# Led_sensor_board_wiring.net
KiCad netlist of a schematic drawn in Altium Designer
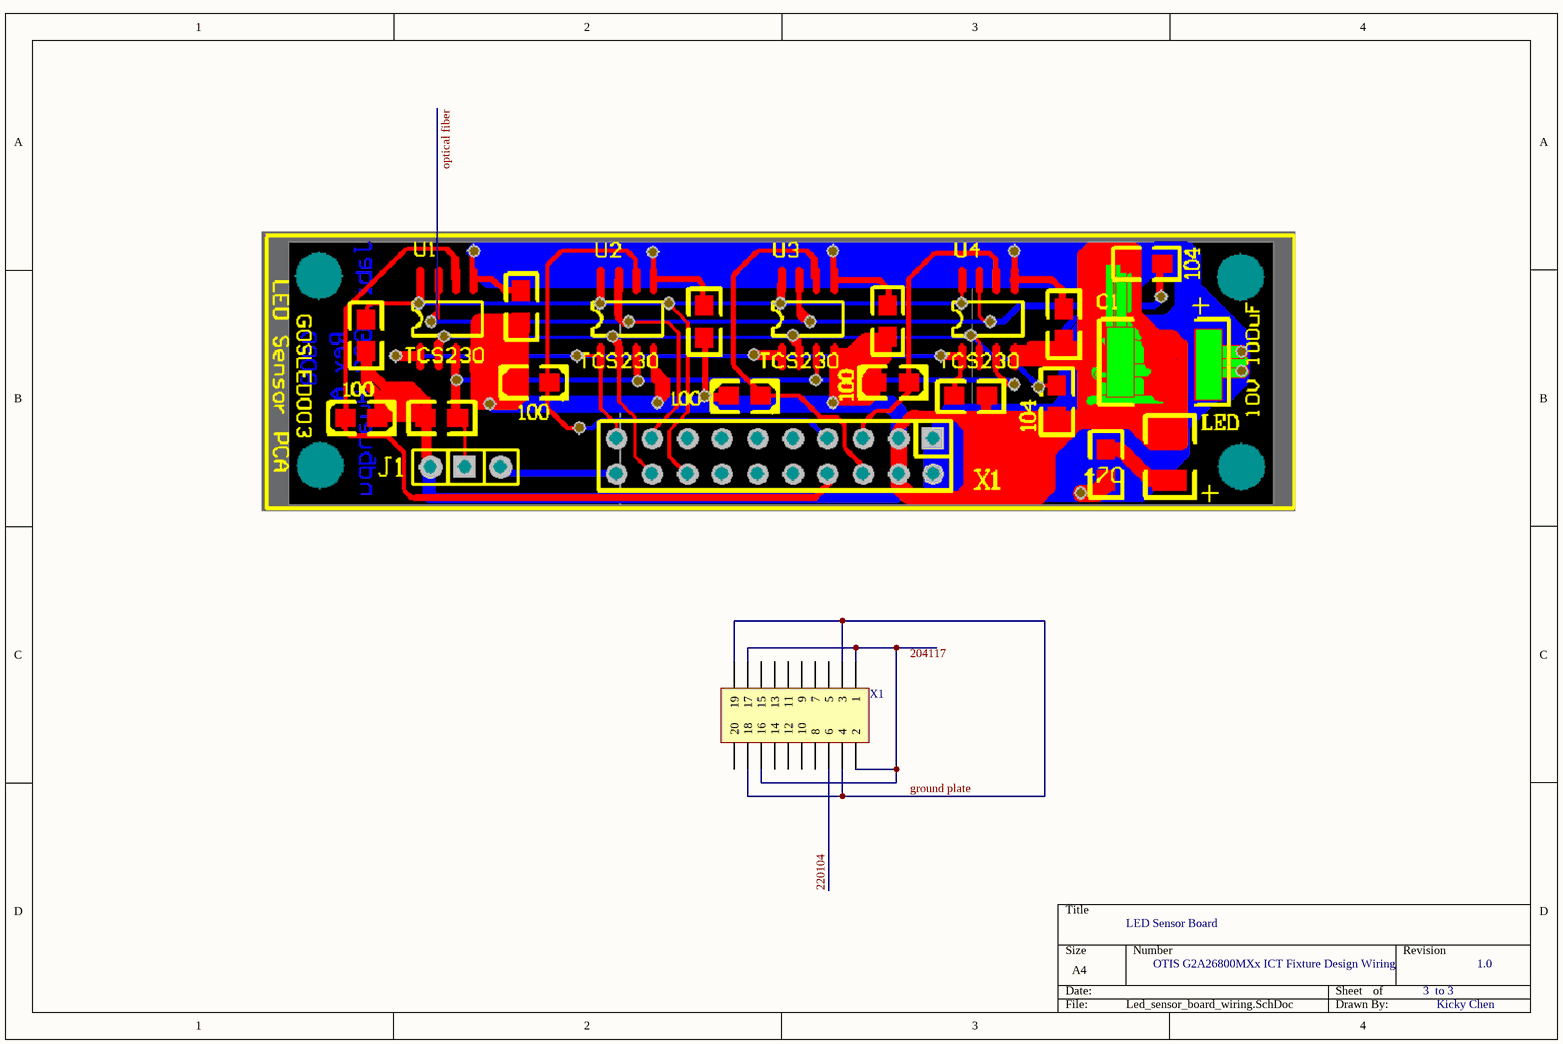
[diagram p0: Led_sensor_board_wiring.SchDoc]

(export (version "E")
  (design (tool "Eeschema 10.0.6"))
  (components
    (comp (ref "X1")
      (value "Header 10X2")
      (footprint "HDR2X10")
      (description "Header, 10-Pin, Dual row")
      (fields (field (name "PUBLISHER") "Altium Limited"))
      (libsource (lib "Miscellaneous Connectors") (part "Header 10X2"))
    )
  )
  (nets
    (net (code "2") (name "/220104") (class "Default")
      (node (ref "X1") (pin "6") (pinfunction "6_6") (pintype "passive"))
    )
    (net (code "3") (name "/ground plate") (class "Default")
      (node (ref "X1") (pin "18") (pinfunction "18_18") (pintype "passive"))
      (node (ref "X1") (pin "19") (pinfunction "19_19") (pintype "passive"))
      (node (ref "X1") (pin "3") (pinfunction "3_3") (pintype "passive"))
      (node (ref "X1") (pin "4") (pinfunction "4_4") (pintype "passive"))
    )
    (net (code "5") (name "Net-(X1-Pad1)") (class "Default")
      (node (ref "X1") (pin "1") (pinfunction "1_1") (pintype "passive"))
      (node (ref "X1") (pin "16") (pinfunction "16_16") (pintype "passive"))
      (node (ref "X1") (pin "17") (pinfunction "17_17") (pintype "passive"))
      (node (ref "X1") (pin "2") (pinfunction "2_2") (pintype "passive"))
    )
    (net (code "6") (name "unconnected-(X1-Pad5)") (class "Default")
      (node (ref "X1") (pin "5") (pinfunction "5_5") (pintype "passive"))
    )
    (net (code "7") (name "unconnected-(X1-Pad7)") (class "Default")
      (node (ref "X1") (pin "7") (pinfunction "7_7") (pintype "passive"))
    )
    (net (code "8") (name "unconnected-(X1-Pad8)") (class "Default")
      (node (ref "X1") (pin "8") (pinfunction "8_8") (pintype "passive"))
    )
    (net (code "9") (name "unconnected-(X1-Pad9)") (class "Default")
      (node (ref "X1") (pin "9") (pinfunction "9_9") (pintype "passive"))
    )
    (net (code "10") (name "unconnected-(X1-Pad10)") (class "Default")
      (node (ref "X1") (pin "10") (pinfunction "10_10") (pintype "passive"))
    )
    (net (code "11") (name "unconnected-(X1-Pad11)") (class "Default")
      (node (ref "X1") (pin "11") (pinfunction "11_11") (pintype "passive"))
    )
    (net (code "12") (name "unconnected-(X1-Pad12)") (class "Default")
      (node (ref "X1") (pin "12") (pinfunction "12_12") (pintype "passive"))
    )
    (net (code "13") (name "unconnected-(X1-Pad13)") (class "Default")
      (node (ref "X1") (pin "13") (pinfunction "13_13") (pintype "passive"))
    )
    (net (code "14") (name "unconnected-(X1-Pad14)") (class "Default")
      (node (ref "X1") (pin "14") (pinfunction "14_14") (pintype "passive"))
    )
    (net (code "15") (name "unconnected-(X1-Pad15)") (class "Default")
      (node (ref "X1") (pin "15") (pinfunction "15_15") (pintype "passive"))
    )
    (net (code "16") (name "unconnected-(X1-Pad20)") (class "Default")
      (node (ref "X1") (pin "20") (pinfunction "20_20") (pintype "passive"))
    )
  )
)
